# LightSensorsButtons.net
KiCad netlist of a schematic drawn in Altium Designer
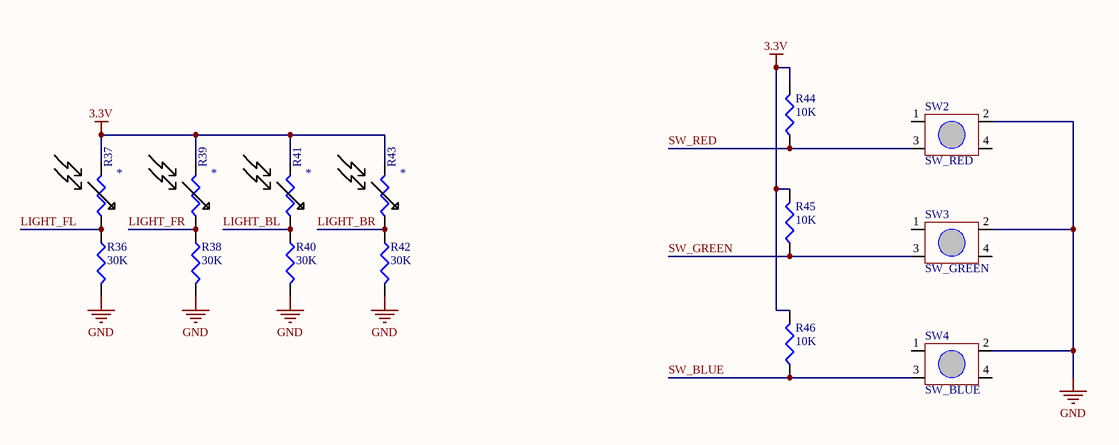
[diagram p0: LightSensorsButtons.SchDoc]

(export (version "E")
  (design (tool "Eeschema 10.0.6"))
  (components
    (comp (ref "R36")
      (value "30K")
      (footprint "RESC1608L")
      (description "Resistor")
      (fields (field (name "Comment") "Res3") (field (name "PUBLISHER") "Altium Limited"))
      (libsource (lib "Miscellaneous Devices") (part "Res3"))
    )
    (comp (ref "R37")
      (value "photoresistor")
      (footprint "photoresistor")
      (fields (field (name "ALTIUM_VALUE") "*"))
      (libsource (lib "mrone") (part "photoresistor"))
    )
    (comp (ref "R38")
      (value "30K")
      (footprint "RESC1608L")
      (description "Resistor")
      (fields (field (name "Comment") "Res3") (field (name "PUBLISHER") "Altium Limited"))
      (libsource (lib "Miscellaneous Devices") (part "Res3"))
    )
    (comp (ref "R39")
      (value "photoresistor")
      (footprint "photoresistor")
      (fields (field (name "ALTIUM_VALUE") "*"))
      (libsource (lib "mrone") (part "photoresistor"))
    )
    (comp (ref "R40")
      (value "30K")
      (footprint "RESC1608L")
      (description "Resistor")
      (fields (field (name "Comment") "Res3") (field (name "PUBLISHER") "Altium Limited"))
      (libsource (lib "Miscellaneous Devices") (part "Res3"))
    )
    (comp (ref "R41")
      (value "photoresistor")
      (footprint "photoresistor")
      (fields (field (name "ALTIUM_VALUE") "*"))
      (libsource (lib "mrone") (part "photoresistor"))
    )
    (comp (ref "R42")
      (value "30K")
      (footprint "RESC1608L")
      (description "Resistor")
      (fields (field (name "Comment") "Res3") (field (name "PUBLISHER") "Altium Limited"))
      (libsource (lib "Miscellaneous Devices") (part "Res3"))
    )
    (comp (ref "R43")
      (value "photoresistor")
      (footprint "photoresistor")
      (fields (field (name "ALTIUM_VALUE") "*"))
      (libsource (lib "mrone") (part "photoresistor"))
    )
    (comp (ref "R44")
      (value "10K")
      (footprint "RESC1608L")
      (description "Resistor")
      (fields (field (name "Comment") "Res3") (field (name "PUBLISHER") "Altium Limited"))
      (libsource (lib "Miscellaneous Devices") (part "Res3"))
    )
    (comp (ref "R45")
      (value "10K")
      (footprint "RESC1608L")
      (description "Resistor")
      (fields (field (name "Comment") "Res3") (field (name "PUBLISHER") "Altium Limited"))
      (libsource (lib "Miscellaneous Devices") (part "Res3"))
    )
    (comp (ref "R46")
      (value "10K")
      (footprint "RESC1608L")
      (description "Resistor")
      (fields (field (name "Comment") "Res3") (field (name "PUBLISHER") "Altium Limited"))
      (libsource (lib "Miscellaneous Devices") (part "Res3"))
    )
    (comp (ref "SW2")
      (value "SW_RED")
      (footprint "SwitchTall-TL330")
      (libsource (lib "mrone") (part "Switch-TL330"))
    )
    (comp (ref "SW3")
      (value "SW_GREEN")
      (footprint "SwitchTall-TL330")
      (libsource (lib "mrone") (part "Switch-TL330"))
    )
    (comp (ref "SW4")
      (value "SW_BLUE")
      (footprint "SwitchTall-TL330")
      (libsource (lib "mrone") (part "Switch-TL330"))
    )
  )
  (nets
    (net (code "1") (name "/LIGHT_BL") (class "Default")
      (node (ref "R40") (pin "1") (pinfunction "1_1") (pintype "passive"))
      (node (ref "R41") (pin "1") (pinfunction "1_1") (pintype "passive"))
    )
    (net (code "2") (name "/LIGHT_BR") (class "Default")
      (node (ref "R42") (pin "1") (pinfunction "1_1") (pintype "passive"))
      (node (ref "R43") (pin "1") (pinfunction "1_1") (pintype "passive"))
    )
    (net (code "3") (name "/LIGHT_FL") (class "Default")
      (node (ref "R36") (pin "1") (pinfunction "1_1") (pintype "passive"))
      (node (ref "R37") (pin "1") (pinfunction "1_1") (pintype "passive"))
    )
    (net (code "4") (name "/LIGHT_FR") (class "Default")
      (node (ref "R38") (pin "1") (pinfunction "1_1") (pintype "passive"))
      (node (ref "R39") (pin "1") (pinfunction "1_1") (pintype "passive"))
    )
    (net (code "5") (name "/SW_BLUE") (class "Default")
      (node (ref "R46") (pin "1") (pinfunction "1_1") (pintype "passive"))
      (node (ref "SW4") (pin "3") (pinfunction "3_3") (pintype "passive"))
    )
    (net (code "6") (name "/SW_GREEN") (class "Default")
      (node (ref "R45") (pin "1") (pinfunction "1_1") (pintype "passive"))
      (node (ref "SW3") (pin "3") (pinfunction "3_3") (pintype "passive"))
    )
    (net (code "7") (name "/SW_RED") (class "Default")
      (node (ref "R44") (pin "1") (pinfunction "1_1") (pintype "passive"))
      (node (ref "SW2") (pin "3") (pinfunction "3_3") (pintype "passive"))
    )
    (net (code "8") (name "3.3V") (class "Default")
      (node (ref "R37") (pin "2") (pinfunction "2_2") (pintype "passive"))
      (node (ref "R39") (pin "2") (pinfunction "2_2") (pintype "passive"))
      (node (ref "R41") (pin "2") (pinfunction "2_2") (pintype "passive"))
      (node (ref "R43") (pin "2") (pinfunction "2_2") (pintype "passive"))
      (node (ref "R44") (pin "2") (pinfunction "2_2") (pintype "passive"))
      (node (ref "R45") (pin "2") (pinfunction "2_2") (pintype "passive"))
      (node (ref "R46") (pin "2") (pinfunction "2_2") (pintype "passive"))
    )
    (net (code "9") (name "GND") (class "Default")
      (node (ref "R36") (pin "2") (pinfunction "2_2") (pintype "passive"))
      (node (ref "R38") (pin "2") (pinfunction "2_2") (pintype "passive"))
      (node (ref "R40") (pin "2") (pinfunction "2_2") (pintype "passive"))
      (node (ref "R42") (pin "2") (pinfunction "2_2") (pintype "passive"))
      (node (ref "SW2") (pin "2") (pinfunction "2_2") (pintype "passive"))
      (node (ref "SW3") (pin "2") (pinfunction "2_2") (pintype "passive"))
      (node (ref "SW4") (pin "2") (pinfunction "2_2") (pintype "passive"))
    )
    (net (code "10") (name "unconnected-(SW2-Pad1)") (class "Default")
      (node (ref "SW2") (pin "1") (pinfunction "1_1") (pintype "passive"))
    )
    (net (code "11") (name "unconnected-(SW2-Pad4)") (class "Default")
      (node (ref "SW2") (pin "4") (pinfunction "4_4") (pintype "passive"))
    )
    (net (code "12") (name "unconnected-(SW3-Pad1)") (class "Default")
      (node (ref "SW3") (pin "1") (pinfunction "1_1") (pintype "passive"))
    )
    (net (code "13") (name "unconnected-(SW3-Pad4)") (class "Default")
      (node (ref "SW3") (pin "4") (pinfunction "4_4") (pintype "passive"))
    )
    (net (code "14") (name "unconnected-(SW4-Pad1)") (class "Default")
      (node (ref "SW4") (pin "1") (pinfunction "1_1") (pintype "passive"))
    )
    (net (code "15") (name "unconnected-(SW4-Pad4)") (class "Default")
      (node (ref "SW4") (pin "4") (pinfunction "4_4") (pintype "passive"))
    )
  )
)
